# TPS71710DCKT.net
KiCad netlist of a schematic drawn in Altium Designer
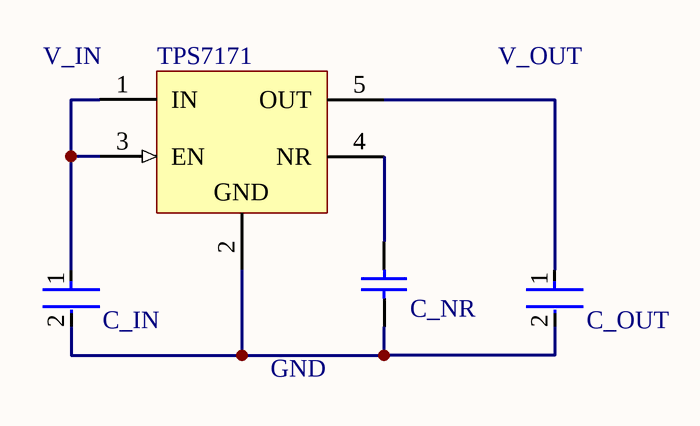
[diagram p0: TPS71710DCKT.SchDoc]

(export (version "E")
  (design (tool "Eeschema 10.0.6"))
  (components
    (comp (ref "C_IN")
      (value "06036D105KAT2A")
      (footprint "FP-0603-L_1_6_0_15-W_0_81-IPC_A")
      (description "General Purpose Ceramic Capacitor, 0603, 1uF, 10%, X5R, 15%, 6.3V")
      (fields (field (name "VOLTAGE") "6.3V") (field (name "TOLERANCE") "10%"))
      (libsource (lib "Altium Content Vault") (part "02cd4be3c70576c341d710602a673aa"))
    )
    (comp (ref "C_NR")
      (value "VJ0603Y104KXXAP")
      (footprint "CAPC1608X92X38NL15T08")
      (fields (field (name "MANUFACTURER") "Vitramon"))
      (libsource (lib "Altium Content Vault") (part "CAP"))
    )
    (comp (ref "C_OUT")
      (value "06036D105KAT2A")
      (footprint "FP-0603-L_1_6_0_15-W_0_81-IPC_A")
      (description "General Purpose Ceramic Capacitor, 0603, 1uF, 10%, X5R, 15%, 6.3V")
      (fields (field (name "VOLTAGE") "6.3V") (field (name "TOLERANCE") "10%"))
      (libsource (lib "Altium Content Vault") (part "02cd4be3c70576c341d710602a673aa"))
    )
    (comp (ref "TPS7171")
      (value "TPS71710DCKT")
      (footprint "DCK0005A_M")
      (fields (field (name "MANUFACTURER") "Texas Instruments"))
      (libsource (lib "Altium Content Vault") (part "TI-TPS79NXX-YYSOT5"))
    )
  )
  (nets
    (net (code "1") (name "Net-(TPS7171-EN)") (class "Default")
      (node (ref "C_IN") (pin "1") (pinfunction "1_1") (pintype "passive"))
      (node (ref "TPS7171") (pin "1") (pinfunction "IN_1") (pintype "power_in"))
      (node (ref "TPS7171") (pin "3") (pinfunction "EN_3") (pintype "input"))
    )
    (net (code "2") (name "Net-(TPS7171-GND)") (class "Default")
      (node (ref "C_IN") (pin "2") (pinfunction "2_2") (pintype "passive"))
      (node (ref "C_NR") (pin "1") (pinfunction "1_1") (pintype "passive"))
      (node (ref "C_OUT") (pin "2") (pinfunction "2_2") (pintype "passive"))
      (node (ref "TPS7171") (pin "2") (pinfunction "GND_2") (pintype "power_in"))
    )
    (net (code "3") (name "Net-(TPS7171-NR)") (class "Default")
      (node (ref "C_NR") (pin "2") (pinfunction "2_2") (pintype "passive"))
      (node (ref "TPS7171") (pin "4") (pinfunction "NR_4") (pintype "passive"))
    )
    (net (code "4") (name "Net-(TPS7171-OUT)") (class "Default")
      (node (ref "C_OUT") (pin "1") (pinfunction "1_1") (pintype "passive"))
      (node (ref "TPS7171") (pin "5") (pinfunction "OUT_5") (pintype "power_in"))
    )
  )
)
